# Regelaar.net
KiCad netlist of a schematic drawn in Altium Designer
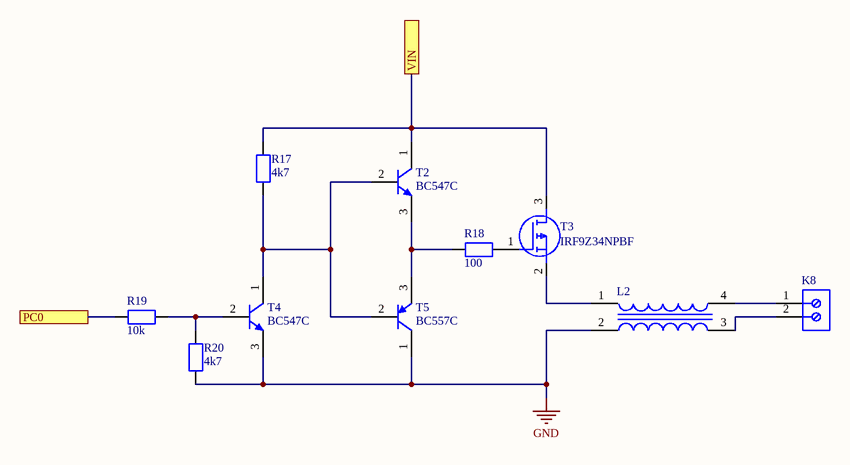
[diagram p0: Regelaar.SchDoc]

(export (version "E")
  (design (tool "Eeschema 10.0.6"))
  (components
    (comp (ref "K8")
      (value "~")
      (footprint "Shroefconnecter")
      (description "Female Header, Pitch 5 mm, 1 x 2 Position, Height 10 mm, Tail Length 3.5 mm, Rohs, Bulk")
      (fields (field (name "VOLTAGE") "300V") (field (name "MANUFACTURER") "TE Connectivity"))
      (libsource (lib "Soldeerstation Schematic") (part "Schroefconnector"))
    )
    (comp (ref "L2")
      (value "~")
      (footprint "Soldeerstation PCB:Common mode smoorspoel")
      (description "Transformer CM2545X171B-10")
      (fields (field (name "MANUFACTURER_PART_NUMBER") "CM2545X171B-10"))
      (libsource (lib "Soldeerstation Schematic") (part "Smoorspoel commom mode"))
    )
    (comp (ref "R17")
      (value "4k7")
      (footprint "Resistor")
      (fields (field (name "MANUFACTURER") "Vishay Dale") (field (name "PART NUMBER") "CRCW08050000Z0EA"))
      (libsource (lib "Soldeerstation Schematic") (part "Resistor"))
    )
    (comp (ref "R18")
      (value "100")
      (footprint "Resistor")
      (fields (field (name "MANUFACTURER") "Vishay Dale") (field (name "PART NUMBER") "CRCW08050000Z0EA"))
      (libsource (lib "Soldeerstation Schematic") (part "Resistor"))
    )
    (comp (ref "R19")
      (value "10k")
      (footprint "Resistor")
      (fields (field (name "MANUFACTURER") "Vishay Dale") (field (name "PART NUMBER") "CRCW08050000Z0EA"))
      (libsource (lib "Soldeerstation Schematic") (part "Resistor"))
    )
    (comp (ref "R20")
      (value "4k7")
      (footprint "Resistor")
      (fields (field (name "MANUFACTURER") "Vishay Dale") (field (name "PART NUMBER") "CRCW08050000Z0EA"))
      (libsource (lib "Soldeerstation Schematic") (part "Resistor"))
    )
    (comp (ref "T2")
      (value "BC547C")
      (footprint "BC547C")
      (description "Amplifier Transistor, NPN Silicon, 3-Pin TO-92, Bulk Box")
      (fields (field (name "MANUFACTURER") "On Semiconductor"))
      (libsource (lib "Soldeerstation Schematic") (part "BC547C"))
    )
    (comp (ref "T3")
      (value "IRF9Z34NPBF")
      (footprint "Soldeerstation PCB:MOSFET")
      (description "MOSFET (P-Channel)")
      (fields (field (name "MOUSER2 PART NUMBER") "942-IRF9Z34NPBF"))
      (libsource (lib "Soldeerstation Schematic") (part "MOSFET"))
    )
    (comp (ref "T4")
      (value "BC547C")
      (footprint "BC547C")
      (description "Amplifier Transistor, NPN Silicon, 3-Pin TO-92, Bulk Box")
      (fields (field (name "MANUFACTURER") "On Semiconductor"))
      (libsource (lib "Soldeerstation Schematic") (part "BC547C"))
    )
    (comp (ref "T5")
      (value "BC557C")
      (footprint "BC557C")
      (description "Amplifier Transistor, PNP Silicon, 3-Pin TO-92, Bulk Box")
      (fields (field (name "MANUFACTURER") "On Semiconductor"))
      (libsource (lib "Soldeerstation Schematic") (part "BC557C"))
    )
  )
  (nets
    (net (code "1") (name "/PC0") (class "Default")
      (node (ref "R19") (pin "1") (pinfunction "1_1") (pintype "passive"))
    )
    (net (code "2") (name "/VIN") (class "Default")
      (node (ref "R17") (pin "2") (pinfunction "2_2") (pintype "passive"))
      (node (ref "T2") (pin "1") (pinfunction "C_1") (pintype "passive"))
      (node (ref "T3") (pin "3") (pinfunction "D_3") (pintype "passive"))
    )
    (net (code "3") (name "GND") (class "Default")
      (node (ref "L2") (pin "2") (pinfunction "SEC+_2") (pintype "passive"))
      (node (ref "R20") (pin "1") (pinfunction "1_1") (pintype "passive"))
      (node (ref "T4") (pin "3") (pinfunction "E_3") (pintype "passive"))
      (node (ref "T5") (pin "1") (pinfunction "C_1") (pintype "passive"))
    )
    (net (code "4") (name "Net-(L2-PRI+)") (class "Default")
      (node (ref "L2") (pin "1") (pinfunction "PRI+_1") (pintype "passive"))
      (node (ref "T3") (pin "2") (pinfunction "S_2") (pintype "passive"))
    )
    (net (code "5") (name "Net-(L2-PRI-)") (class "Default")
      (node (ref "K8") (pin "1") (pinfunction "1_1") (pintype "passive"))
      (node (ref "L2") (pin "4") (pinfunction "PRI-_4") (pintype "passive"))
    )
    (net (code "6") (name "Net-(L2-SEC-)") (class "Default")
      (node (ref "K8") (pin "2") (pinfunction "2_2") (pintype "passive"))
      (node (ref "L2") (pin "3") (pinfunction "SEC-_3") (pintype "passive"))
    )
    (net (code "7") (name "Net-(T2-B)") (class "Default")
      (node (ref "R17") (pin "1") (pinfunction "1_1") (pintype "passive"))
      (node (ref "T2") (pin "2") (pinfunction "B_2") (pintype "passive"))
      (node (ref "T4") (pin "1") (pinfunction "C_1") (pintype "passive"))
      (node (ref "T5") (pin "2") (pinfunction "B_2") (pintype "passive"))
    )
    (net (code "8") (name "Net-(T2-E)") (class "Default")
      (node (ref "R18") (pin "1") (pinfunction "1_1") (pintype "passive"))
      (node (ref "T2") (pin "3") (pinfunction "E_3") (pintype "passive"))
      (node (ref "T5") (pin "3") (pinfunction "E_3") (pintype "passive"))
    )
    (net (code "9") (name "Net-(T3-G)") (class "Default")
      (node (ref "R18") (pin "2") (pinfunction "2_2") (pintype "passive"))
      (node (ref "T3") (pin "1") (pinfunction "G_1") (pintype "passive"))
    )
    (net (code "10") (name "Net-(T4-B)") (class "Default")
      (node (ref "R19") (pin "2") (pinfunction "2_2") (pintype "passive"))
      (node (ref "R20") (pin "2") (pinfunction "2_2") (pintype "passive"))
      (node (ref "T4") (pin "2") (pinfunction "B_2") (pintype "passive"))
    )
  )
)
